# act.net
KiCad netlist of a schematic drawn in EAGLE
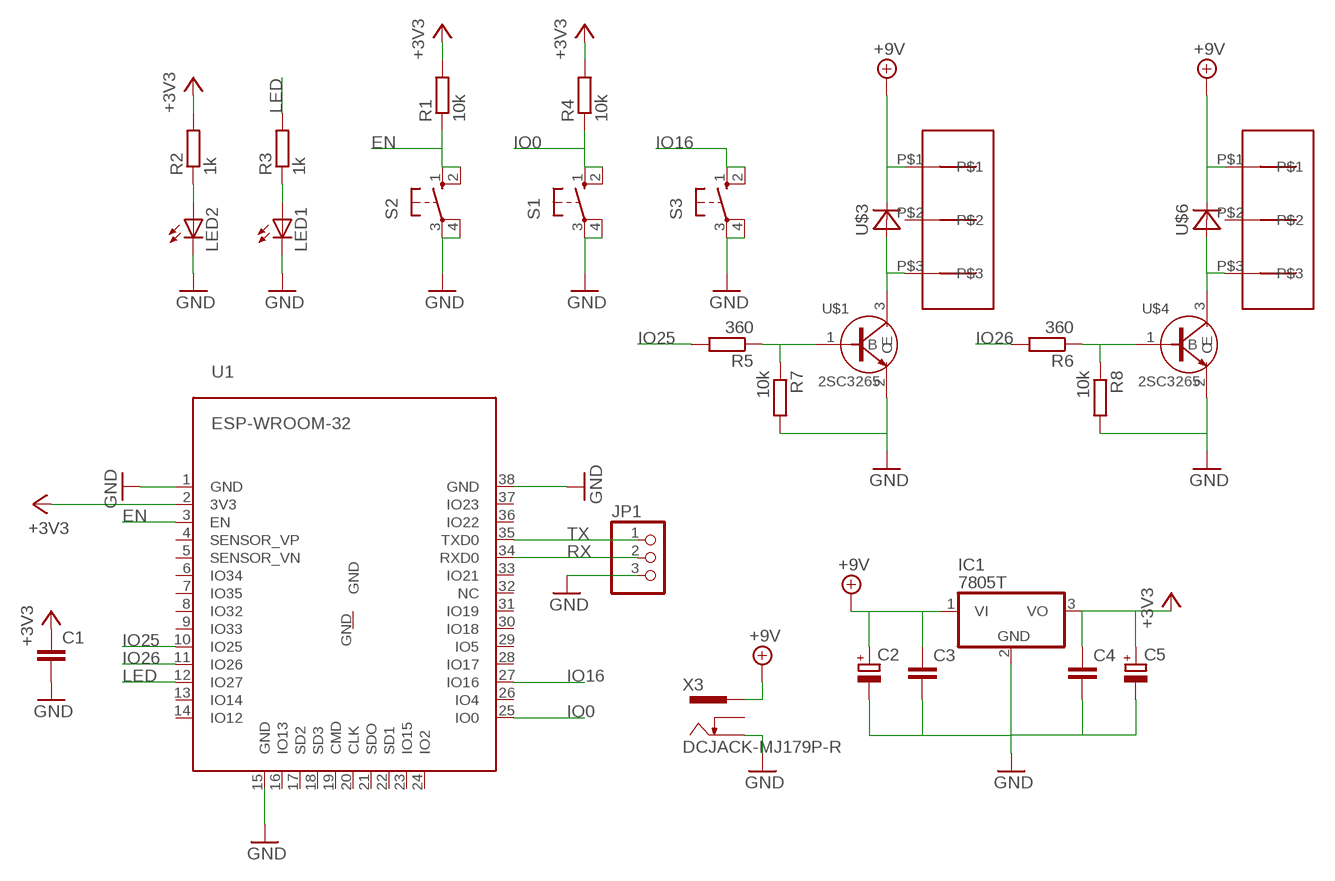
[diagram p0: schematic, sheet 1]

(export (version "E")
  (design (tool "Eeschema 10.0.6"))
  (components
    (comp (ref "C1")
      (value "C-EU050-024X044")
      (footprint "eagle-import:C050-024X044")
      (libsource (lib "eagle-import") (part "C-EU050-024X044"))
    )
    (comp (ref "C2")
      (value "CPOL-EUE5-4")
      (footprint "eagle-import:E5-4")
      (libsource (lib "eagle-import") (part "CPOL-EUE5-4"))
    )
    (comp (ref "C3")
      (value "C-EU050-024X044")
      (footprint "eagle-import:C050-024X044")
      (libsource (lib "eagle-import") (part "C-EU050-024X044"))
    )
    (comp (ref "C4")
      (value "C-EU050-024X044")
      (footprint "eagle-import:C050-024X044")
      (libsource (lib "eagle-import") (part "C-EU050-024X044"))
    )
    (comp (ref "C5")
      (value "CPOL-EUE5-4")
      (footprint "eagle-import:E5-4")
      (libsource (lib "eagle-import") (part "CPOL-EUE5-4"))
    )
    (comp (ref "IC1")
      (value "7805T")
      (footprint "eagle-import:TO220H")
      (libsource (lib "eagle-import") (part "78T05"))
    )
    (comp (ref "JP1")
      (value "PINHD-1X3/90")
      (footprint "eagle-import:1X03_90")
      (libsource (lib "eagle-import") (part "PINHD-1X3/90"))
    )
    (comp (ref "LED1")
      (value "LEDSML0603")
      (footprint "eagle-import:SML0603")
      (libsource (lib "eagle-import") (part "LEDSML0603"))
    )
    (comp (ref "LED2")
      (value "LEDSML0603")
      (footprint "eagle-import:SML0603")
      (libsource (lib "eagle-import") (part "LEDSML0603"))
    )
    (comp (ref "R1")
      (value "10k")
      (footprint "eagle-import:0207_10")
      (libsource (lib "eagle-import") (part "R-EU_0207/10"))
    )
    (comp (ref "R2")
      (value "1k")
      (footprint "eagle-import:0207_10")
      (libsource (lib "eagle-import") (part "R-EU_0207/10"))
    )
    (comp (ref "R3")
      (value "1k")
      (footprint "eagle-import:0207_10")
      (libsource (lib "eagle-import") (part "R-EU_0207/10"))
    )
    (comp (ref "R4")
      (value "10k")
      (footprint "eagle-import:0207_10")
      (libsource (lib "eagle-import") (part "R-EU_0207/10"))
    )
    (comp (ref "R5")
      (value "360")
      (footprint "eagle-import:0207_10")
      (libsource (lib "eagle-import") (part "R-EU_0207/10"))
    )
    (comp (ref "R6")
      (value "360")
      (footprint "eagle-import:0207_10")
      (libsource (lib "eagle-import") (part "R-EU_0207/10"))
    )
    (comp (ref "R7")
      (value "10k")
      (footprint "eagle-import:0207_10")
      (libsource (lib "eagle-import") (part "R-EU_0207/10"))
    )
    (comp (ref "R8")
      (value "10k")
      (footprint "eagle-import:0207_10")
      (libsource (lib "eagle-import") (part "R-EU_0207/10"))
    )
    (comp (ref "S1")
      (value "10-XX")
      (footprint "eagle-import:B3F-10XX")
      (fields (field (name "MPN") "B3F-1000"))
      (libsource (lib "eagle-import") (part "10-XX"))
    )
    (comp (ref "S2")
      (value "10-XX")
      (footprint "eagle-import:B3F-10XX")
      (fields (field (name "MPN") "B3F-1000"))
      (libsource (lib "eagle-import") (part "10-XX"))
    )
    (comp (ref "S3")
      (value "10-XX")
      (footprint "eagle-import:B3F-10XX")
      (fields (field (name "MPN") "B3F-1000"))
      (libsource (lib "eagle-import") (part "10-XX"))
    )
    (comp (ref "U$1")
      (value "2SC3265")
      (footprint "eagle-import:SC-59")
      (libsource (lib "eagle-import") (part "2SC3265"))
    )
    (comp (ref "U$2")
      (value "JST_NH")
      (footprint "eagle-import:JST_NH")
      (libsource (lib "eagle-import") (part "JST_NH"))
    )
    (comp (ref "U$3")
      (value "GP20B")
      (footprint "eagle-import:GP20B")
      (libsource (lib "eagle-import") (part "GP20B"))
    )
    (comp (ref "U$4")
      (value "2SC3265")
      (footprint "eagle-import:SC-59")
      (libsource (lib "eagle-import") (part "2SC3265"))
    )
    (comp (ref "U$5")
      (value "JST_NH")
      (footprint "eagle-import:JST_NH")
      (libsource (lib "eagle-import") (part "JST_NH"))
    )
    (comp (ref "U$6")
      (value "GP20B")
      (footprint "eagle-import:GP20B")
      (libsource (lib "eagle-import") (part "GP20B"))
    )
    (comp (ref "U1")
      (value "ESP-WROOM-32")
      (footprint "eagle-import:ESP-WROOM-32")
      (libsource (lib "eagle-import") (part "ESP-WROOM-32"))
    )
    (comp (ref "X3")
      (value "DCJACK-MJ179P-R")
      (footprint "eagle-import:MJ-179P-R")
      (libsource (lib "eagle-import") (part "DCJACK-MJ179P-R"))
    )
  )
  (nets
    (net (code "1") (name "+3V3") (class "Default")
      (node (ref "C1") (pin "1") (pinfunction "1_1") (pintype "passive"))
      (node (ref "C4") (pin "1") (pinfunction "1_1") (pintype "passive"))
      (node (ref "C5") (pin "+") (pinfunction "+_+") (pintype "passive"))
      (node (ref "IC1") (pin "3") (pinfunction "VO_3") (pintype "passive"))
      (node (ref "R1") (pin "2") (pinfunction "2_2") (pintype "passive"))
      (node (ref "R2") (pin "2") (pinfunction "2_2") (pintype "passive"))
      (node (ref "R4") (pin "2") (pinfunction "2_2") (pintype "passive"))
      (node (ref "U1") (pin "2") (pinfunction "3V3_2") (pintype "bidirectional"))
    )
    (net (code "2") (name "+9V") (class "Default")
      (node (ref "C2") (pin "+") (pinfunction "+_+") (pintype "passive"))
      (node (ref "C3") (pin "1") (pinfunction "1_1") (pintype "passive"))
      (node (ref "IC1") (pin "1") (pinfunction "VI_1") (pintype "input"))
      (node (ref "U$2") (pin "P$1") (pinfunction "P$1_P$1") (pintype "bidirectional"))
      (node (ref "U$3") (pin "K") (pinfunction "C_K") (pintype "passive"))
      (node (ref "U$5") (pin "P$1") (pinfunction "P$1_P$1") (pintype "bidirectional"))
      (node (ref "U$6") (pin "K") (pinfunction "C_K") (pintype "passive"))
      (node (ref "X3") (pin "1") (pinfunction "1_1") (pintype "passive"))
    )
    (net (code "3") (name "/EN") (class "Default")
      (node (ref "R1") (pin "1") (pinfunction "1_1") (pintype "passive"))
      (node (ref "S2") (pin "1") (pinfunction "S_1") (pintype "passive"))
      (node (ref "S2") (pin "2") (pinfunction "S1_2") (pintype "passive"))
      (node (ref "U1") (pin "3") (pinfunction "EN_3") (pintype "bidirectional"))
    )
    (net (code "4") (name "/IO0") (class "Default")
      (node (ref "R4") (pin "1") (pinfunction "1_1") (pintype "passive"))
      (node (ref "S1") (pin "1") (pinfunction "S_1") (pintype "passive"))
      (node (ref "S1") (pin "2") (pinfunction "S1_2") (pintype "passive"))
      (node (ref "U1") (pin "25") (pinfunction "IO0_25") (pintype "bidirectional"))
    )
    (net (code "5") (name "/IO16") (class "Default")
      (node (ref "S3") (pin "1") (pinfunction "S_1") (pintype "passive"))
      (node (ref "S3") (pin "2") (pinfunction "S1_2") (pintype "passive"))
      (node (ref "U1") (pin "27") (pinfunction "IO16_27") (pintype "bidirectional"))
    )
    (net (code "6") (name "/IO25") (class "Default")
      (node (ref "R5") (pin "2") (pinfunction "2_2") (pintype "passive"))
      (node (ref "U1") (pin "10") (pinfunction "IO25_10") (pintype "bidirectional"))
    )
    (net (code "7") (name "/IO26") (class "Default")
      (node (ref "R6") (pin "2") (pinfunction "2_2") (pintype "passive"))
      (node (ref "U1") (pin "11") (pinfunction "IO26_11") (pintype "bidirectional"))
    )
    (net (code "8") (name "/LED") (class "Default")
      (node (ref "R3") (pin "2") (pinfunction "2_2") (pintype "passive"))
      (node (ref "U1") (pin "12") (pinfunction "IO27_12") (pintype "bidirectional"))
    )
    (net (code "9") (name "/RX") (class "Default")
      (node (ref "JP1") (pin "2") (pinfunction "2_2") (pintype "passive"))
      (node (ref "U1") (pin "34") (pinfunction "RXD0_34") (pintype "bidirectional"))
    )
    (net (code "10") (name "/TX") (class "Default")
      (node (ref "JP1") (pin "1") (pinfunction "1_1") (pintype "passive"))
      (node (ref "U1") (pin "35") (pinfunction "TXD0_35") (pintype "bidirectional"))
    )
    (net (code "11") (name "GND") (class "Default")
      (node (ref "C1") (pin "2") (pinfunction "2_2") (pintype "passive"))
      (node (ref "C2") (pin "-") (pinfunction "-_-") (pintype "passive"))
      (node (ref "C3") (pin "2") (pinfunction "2_2") (pintype "passive"))
      (node (ref "C4") (pin "2") (pinfunction "2_2") (pintype "passive"))
      (node (ref "C5") (pin "-") (pinfunction "-_-") (pintype "passive"))
      (node (ref "IC1") (pin "2") (pinfunction "GND_2") (pintype "passive"))
      (node (ref "JP1") (pin "3") (pinfunction "3_3") (pintype "passive"))
      (node (ref "LED1") (pin "C") (pinfunction "C_C") (pintype "passive"))
      (node (ref "LED2") (pin "C") (pinfunction "C_C") (pintype "passive"))
      (node (ref "R7") (pin "2") (pinfunction "2_2") (pintype "passive"))
      (node (ref "R8") (pin "2") (pinfunction "2_2") (pintype "passive"))
      (node (ref "S1") (pin "3") (pinfunction "P_3") (pintype "passive"))
      (node (ref "S1") (pin "4") (pinfunction "P1_4") (pintype "passive"))
      (node (ref "S2") (pin "3") (pinfunction "P_3") (pintype "passive"))
      (node (ref "S2") (pin "4") (pinfunction "P1_4") (pintype "passive"))
      (node (ref "S3") (pin "3") (pinfunction "P_3") (pintype "passive"))
      (node (ref "S3") (pin "4") (pinfunction "P1_4") (pintype "passive"))
      (node (ref "U$1") (pin "2") (pinfunction "E_2") (pintype "bidirectional"))
      (node (ref "U$4") (pin "2") (pinfunction "E_2") (pintype "bidirectional"))
      (node (ref "U1") (pin "1") (pinfunction "GND_1") (pintype "bidirectional"))
      (node (ref "U1") (pin "15") (pinfunction "GND_15") (pintype "bidirectional"))
      (node (ref "U1") (pin "38") (pinfunction "GND_38") (pintype "bidirectional"))
      (node (ref "X3") (pin "2") (pinfunction "2_2") (pintype "passive"))
    )
    (net (code "12") (name "Net-(LED1-PadA)") (class "Default")
      (node (ref "LED1") (pin "A") (pinfunction "A_A") (pintype "passive"))
      (node (ref "R3") (pin "1") (pinfunction "1_1") (pintype "passive"))
    )
    (net (code "13") (name "Net-(LED2-PadA)") (class "Default")
      (node (ref "LED2") (pin "A") (pinfunction "A_A") (pintype "passive"))
      (node (ref "R2") (pin "1") (pinfunction "1_1") (pintype "passive"))
    )
    (net (code "14") (name "Net-(U$1-B)") (class "Default")
      (node (ref "R5") (pin "1") (pinfunction "1_1") (pintype "passive"))
      (node (ref "R7") (pin "1") (pinfunction "1_1") (pintype "passive"))
      (node (ref "U$1") (pin "1") (pinfunction "B_1") (pintype "bidirectional"))
    )
    (net (code "15") (name "Net-(U$1-C)") (class "Default")
      (node (ref "U$1") (pin "3") (pinfunction "C_3") (pintype "bidirectional"))
      (node (ref "U$2") (pin "P$3") (pinfunction "P$3_P$3") (pintype "bidirectional"))
      (node (ref "U$3") (pin "A") (pinfunction "A_A") (pintype "passive"))
    )
    (net (code "16") (name "Net-(U$4-B)") (class "Default")
      (node (ref "R6") (pin "1") (pinfunction "1_1") (pintype "passive"))
      (node (ref "R8") (pin "1") (pinfunction "1_1") (pintype "passive"))
      (node (ref "U$4") (pin "1") (pinfunction "B_1") (pintype "bidirectional"))
    )
    (net (code "17") (name "Net-(U$4-C)") (class "Default")
      (node (ref "U$4") (pin "3") (pinfunction "C_3") (pintype "bidirectional"))
      (node (ref "U$5") (pin "P$3") (pinfunction "P$3_P$3") (pintype "bidirectional"))
      (node (ref "U$6") (pin "A") (pinfunction "A_A") (pintype "passive"))
    )
    (net (code "18") (name "unconnected-(U$2-PadP$2)") (class "Default")
      (node (ref "U$2") (pin "P$2") (pinfunction "P$2_P$2") (pintype "bidirectional"))
    )
    (net (code "19") (name "unconnected-(U$5-PadP$2)") (class "Default")
      (node (ref "U$5") (pin "P$2") (pinfunction "P$2_P$2") (pintype "bidirectional"))
    )
    (net (code "20") (name "unconnected-(U1-CLK-Pad20)") (class "Default")
      (node (ref "U1") (pin "20") (pinfunction "CLK_20") (pintype "bidirectional"))
    )
    (net (code "21") (name "unconnected-(U1-CMD-Pad19)") (class "Default")
      (node (ref "U1") (pin "19") (pinfunction "CMD_19") (pintype "bidirectional"))
    )
    (net (code "22") (name "unconnected-(U1-IO2-Pad24)") (class "Default")
      (node (ref "U1") (pin "24") (pinfunction "IO2_24") (pintype "bidirectional"))
    )
    (net (code "23") (name "unconnected-(U1-IO4-Pad26)") (class "Default")
      (node (ref "U1") (pin "26") (pinfunction "IO4_26") (pintype "bidirectional"))
    )
    (net (code "24") (name "unconnected-(U1-IO5-Pad29)") (class "Default")
      (node (ref "U1") (pin "29") (pinfunction "IO5_29") (pintype "bidirectional"))
    )
    (net (code "25") (name "unconnected-(U1-IO12-Pad14)") (class "Default")
      (node (ref "U1") (pin "14") (pinfunction "IO12_14") (pintype "bidirectional"))
    )
    (net (code "26") (name "unconnected-(U1-IO13-Pad16)") (class "Default")
      (node (ref "U1") (pin "16") (pinfunction "IO13_16") (pintype "bidirectional"))
    )
    (net (code "27") (name "unconnected-(U1-IO14-Pad13)") (class "Default")
      (node (ref "U1") (pin "13") (pinfunction "IO14_13") (pintype "bidirectional"))
    )
    (net (code "28") (name "unconnected-(U1-IO15-Pad23)") (class "Default")
      (node (ref "U1") (pin "23") (pinfunction "IO15_23") (pintype "bidirectional"))
    )
    (net (code "29") (name "unconnected-(U1-IO17-Pad28)") (class "Default")
      (node (ref "U1") (pin "28") (pinfunction "IO17_28") (pintype "bidirectional"))
    )
    (net (code "30") (name "unconnected-(U1-IO18-Pad30)") (class "Default")
      (node (ref "U1") (pin "30") (pinfunction "IO18_30") (pintype "bidirectional"))
    )
    (net (code "31") (name "unconnected-(U1-IO19-Pad31)") (class "Default")
      (node (ref "U1") (pin "31") (pinfunction "IO19_31") (pintype "bidirectional"))
    )
    (net (code "32") (name "unconnected-(U1-IO21-Pad33)") (class "Default")
      (node (ref "U1") (pin "33") (pinfunction "IO21_33") (pintype "bidirectional"))
    )
    (net (code "33") (name "unconnected-(U1-IO22-Pad36)") (class "Default")
      (node (ref "U1") (pin "36") (pinfunction "IO22_36") (pintype "bidirectional"))
    )
    (net (code "34") (name "unconnected-(U1-IO23-Pad37)") (class "Default")
      (node (ref "U1") (pin "37") (pinfunction "IO23_37") (pintype "bidirectional"))
    )
    (net (code "35") (name "unconnected-(U1-IO32-Pad8)") (class "Default")
      (node (ref "U1") (pin "8") (pinfunction "IO32_8") (pintype "bidirectional"))
    )
    (net (code "36") (name "unconnected-(U1-IO33-Pad9)") (class "Default")
      (node (ref "U1") (pin "9") (pinfunction "IO33_9") (pintype "bidirectional"))
    )
    (net (code "37") (name "unconnected-(U1-IO34-Pad6)") (class "Default")
      (node (ref "U1") (pin "6") (pinfunction "IO34_6") (pintype "bidirectional"))
    )
    (net (code "38") (name "unconnected-(U1-IO35-Pad7)") (class "Default")
      (node (ref "U1") (pin "7") (pinfunction "IO35_7") (pintype "bidirectional"))
    )
    (net (code "39") (name "unconnected-(U1-NC-Pad32)") (class "Default")
      (node (ref "U1") (pin "32") (pinfunction "NC_32") (pintype "bidirectional"))
    )
    (net (code "40") (name "unconnected-(U1-PadGND)") (class "Default")
      (node (ref "U1") (pin "GND") (pinfunction "GND_GND") (pintype "bidirectional"))
    )
    (net (code "41") (name "unconnected-(U1-SD1-Pad22)") (class "Default")
      (node (ref "U1") (pin "22") (pinfunction "SD1_22") (pintype "bidirectional"))
    )
    (net (code "42") (name "unconnected-(U1-SD2-Pad17)") (class "Default")
      (node (ref "U1") (pin "17") (pinfunction "SD2_17") (pintype "bidirectional"))
    )
    (net (code "43") (name "unconnected-(U1-SD3-Pad18)") (class "Default")
      (node (ref "U1") (pin "18") (pinfunction "SD3_18") (pintype "bidirectional"))
    )
    (net (code "44") (name "unconnected-(U1-SDO-Pad21)") (class "Default")
      (node (ref "U1") (pin "21") (pinfunction "SDO_21") (pintype "bidirectional"))
    )
    (net (code "45") (name "unconnected-(U1-SENSOR_VN-Pad5)") (class "Default")
      (node (ref "U1") (pin "5") (pinfunction "SENSOR_VN_5") (pintype "bidirectional"))
    )
    (net (code "46") (name "unconnected-(U1-SENSOR_VP-Pad4)") (class "Default")
      (node (ref "U1") (pin "4") (pinfunction "SENSOR_VP_4") (pintype "bidirectional"))
    )
    (net (code "47") (name "unconnected-(X3-Pad3)") (class "Default")
      (node (ref "X3") (pin "3") (pinfunction "3_3") (pintype "passive"))
    )
  )
)
